# MCU.net
KiCad netlist of a schematic drawn in Altium Designer
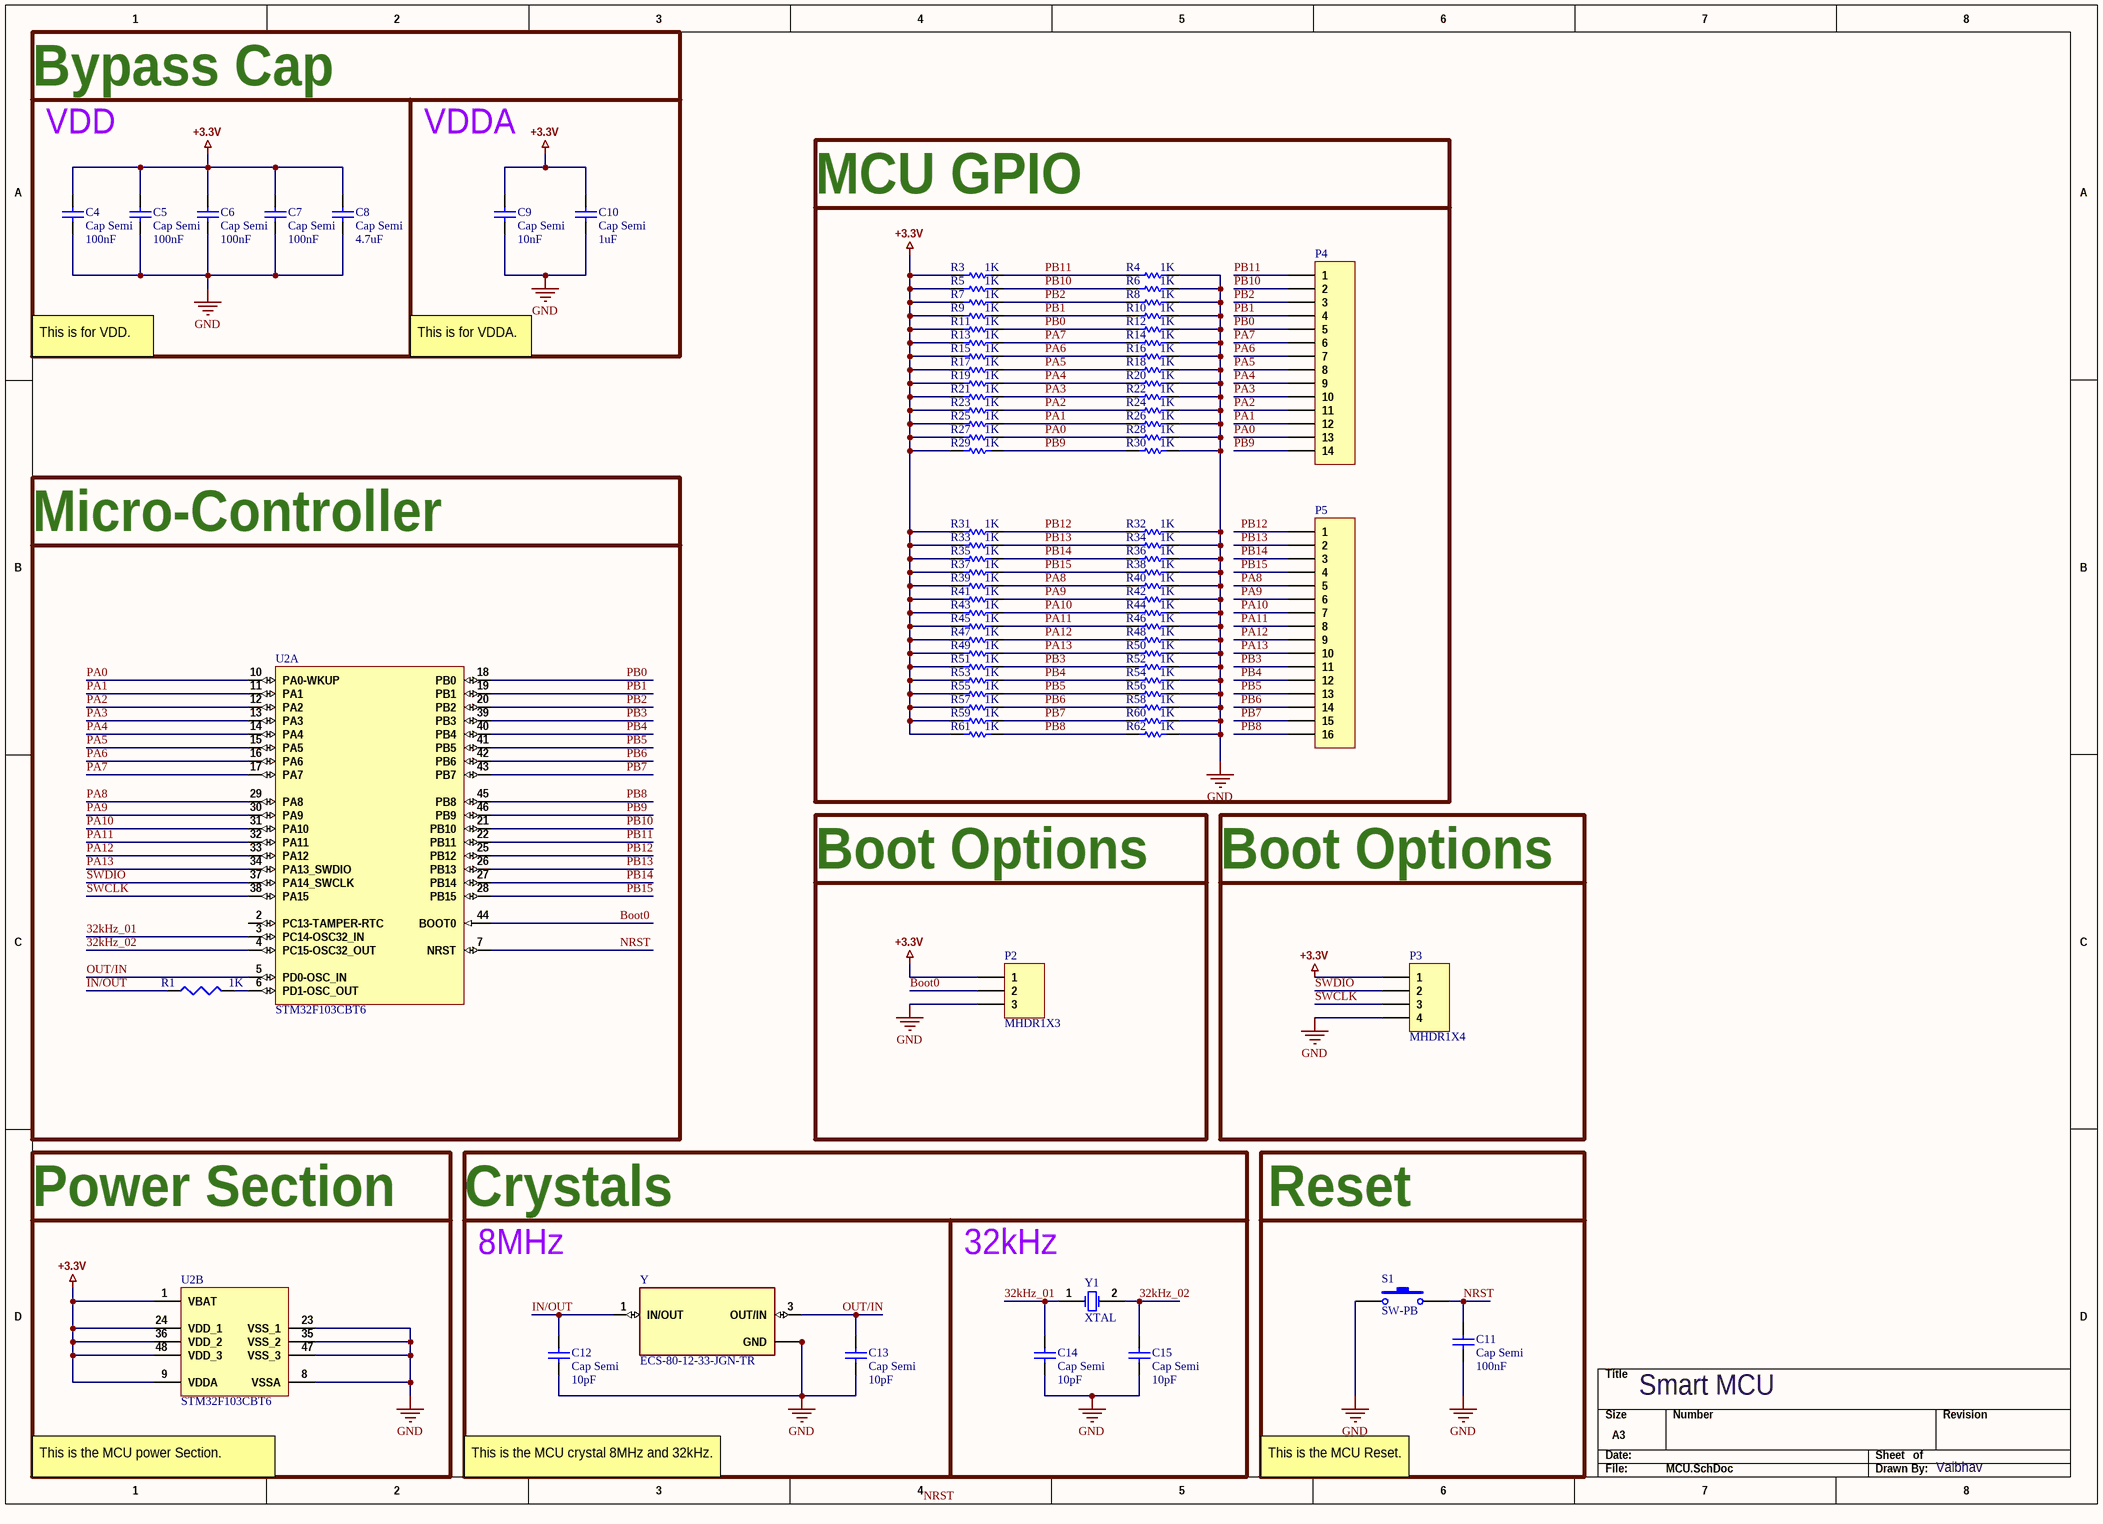
[diagram p0: MCU.SchDoc]

(export (version "E")
  (design (tool "Eeschema 10.0.6"))
  (components
    (comp (ref "C4")
      (value "Cap Semi")
      (footprint "1608[0603]")
      (description "Capacitor (Semiconductor SIM Model)")
      (fields (field (name "ALTIUM_VALUE") "100nF") (field (name "PUBLISHER") "Altium Limited"))
      (libsource (lib "Miscellaneous Devices") (part "Cap Semi"))
    )
    (comp (ref "C5")
      (value "Cap Semi")
      (footprint "1608[0603]")
      (description "Capacitor (Semiconductor SIM Model)")
      (fields (field (name "ALTIUM_VALUE") "100nF") (field (name "PUBLISHER") "Altium Limited"))
      (libsource (lib "Miscellaneous Devices") (part "Cap Semi"))
    )
    (comp (ref "C6")
      (value "Cap Semi")
      (footprint "1608[0603]")
      (description "Capacitor (Semiconductor SIM Model)")
      (fields (field (name "ALTIUM_VALUE") "100nF") (field (name "PUBLISHER") "Altium Limited"))
      (libsource (lib "Miscellaneous Devices") (part "Cap Semi"))
    )
    (comp (ref "C7")
      (value "Cap Semi")
      (footprint "1608[0603]")
      (description "Capacitor (Semiconductor SIM Model)")
      (fields (field (name "ALTIUM_VALUE") "100nF") (field (name "PUBLISHER") "Altium Limited"))
      (libsource (lib "Miscellaneous Devices") (part "Cap Semi"))
    )
    (comp (ref "C8")
      (value "Cap Semi")
      (footprint "1608[0603]")
      (description "Capacitor (Semiconductor SIM Model)")
      (fields (field (name "ALTIUM_VALUE") "4.7uF") (field (name "PUBLISHER") "Altium Limited"))
      (libsource (lib "Miscellaneous Devices") (part "Cap Semi"))
    )
    (comp (ref "C9")
      (value "Cap Semi")
      (footprint "1608[0603]")
      (description "Capacitor (Semiconductor SIM Model)")
      (fields (field (name "ALTIUM_VALUE") "10nF") (field (name "PUBLISHER") "Altium Limited"))
      (libsource (lib "Miscellaneous Devices") (part "Cap Semi"))
    )
    (comp (ref "C10")
      (value "Cap Semi")
      (footprint "1608[0603]")
      (description "Capacitor (Semiconductor SIM Model)")
      (fields (field (name "ALTIUM_VALUE") "1uF") (field (name "PUBLISHER") "Altium Limited"))
      (libsource (lib "Miscellaneous Devices") (part "Cap Semi"))
    )
    (comp (ref "C11")
      (value "Cap Semi")
      (footprint "1608[0603]")
      (description "Capacitor (Semiconductor SIM Model)")
      (fields (field (name "ALTIUM_VALUE") "100nF") (field (name "PUBLISHER") "Altium Limited"))
      (libsource (lib "Miscellaneous Devices") (part "Cap Semi"))
    )
    (comp (ref "C12")
      (value "Cap Semi")
      (footprint "0402")
      (description "Capacitor (Semiconductor SIM Model)")
      (fields (field (name "ALTIUM_VALUE") "10pF") (field (name "PUBLISHER") "Altium Limited"))
      (libsource (lib "Miscellaneous Devices") (part "Cap Semi"))
    )
    (comp (ref "C13")
      (value "Cap Semi")
      (footprint "0402")
      (description "Capacitor (Semiconductor SIM Model)")
      (fields (field (name "ALTIUM_VALUE") "10pF") (field (name "PUBLISHER") "Altium Limited"))
      (libsource (lib "Miscellaneous Devices") (part "Cap Semi"))
    )
    (comp (ref "C14")
      (value "Cap Semi")
      (footprint "0402")
      (description "Capacitor (Semiconductor SIM Model)")
      (fields (field (name "ALTIUM_VALUE") "10pF") (field (name "PUBLISHER") "Altium Limited"))
      (libsource (lib "Miscellaneous Devices") (part "Cap Semi"))
    )
    (comp (ref "C15")
      (value "Cap Semi")
      (footprint "0402")
      (description "Capacitor (Semiconductor SIM Model)")
      (fields (field (name "ALTIUM_VALUE") "10pF") (field (name "PUBLISHER") "Altium Limited"))
      (libsource (lib "Miscellaneous Devices") (part "Cap Semi"))
    )
    (comp (ref "P2")
      (value "MHDR1X3")
      (footprint "MHDR1X3")
      (description "Header, 3-Pin")
      (fields (field (name "PUBLISHER") "Altium Limited"))
      (libsource (lib "Miscellaneous Connectors") (part "MHDR1X3"))
    )
    (comp (ref "P3")
      (value "MHDR1X4")
      (footprint "MHDR1X4")
      (description "Header, 4-Pin")
      (fields (field (name "PUBLISHER") "Altium Limited"))
      (libsource (lib "Miscellaneous Connectors") (part "MHDR1X4"))
    )
    (comp (ref "P4")
      (value "Header 14")
      (footprint "MY_FE14")
      (description "Header, 14-Pin")
      (fields (field (name "ASID PART NUMBER") "Header 14-AS"))
      (libsource (lib "Mylib+Rev+4") (part "Header 14"))
    )
    (comp (ref "P5")
      (value "Header 16")
      (footprint "MY_FE16")
      (description "Header, 16-Pin")
      (fields (field (name "ASID PART NUMBER") "Header 16-AS"))
      (libsource (lib "Mylib+Rev+4") (part "Header 16"))
    )
    (comp (ref "R1")
      (value "1K")
      (footprint "J1-0603")
      (description "Resistor")
      (fields (field (name "Comment") "Res3") (field (name "PUBLISHER") "Altium Limited"))
      (libsource (lib "Miscellaneous Devices") (part "Res3"))
    )
    (comp (ref "R3")
      (value "1K")
      (footprint "MY_0603")
      (description "Standard resistor")
      (fields (field (name "ASID PART NUMBER") "Res-AS"))
      (libsource (lib "Mylib+Rev+4") (part "Res"))
    )
    (comp (ref "R4")
      (value "1K")
      (footprint "MY_0603")
      (description "Standard resistor")
      (fields (field (name "ASID PART NUMBER") "Res-AS"))
      (libsource (lib "Mylib+Rev+4") (part "Res"))
    )
    (comp (ref "R5")
      (value "1K")
      (footprint "MY_0603")
      (description "Standard resistor")
      (fields (field (name "ASID PART NUMBER") "Res-AS"))
      (libsource (lib "Mylib+Rev+4") (part "Res"))
    )
    (comp (ref "R6")
      (value "1K")
      (footprint "MY_0603")
      (description "Standard resistor")
      (fields (field (name "ASID PART NUMBER") "Res-AS"))
      (libsource (lib "Mylib+Rev+4") (part "Res"))
    )
    (comp (ref "R7")
      (value "1K")
      (footprint "MY_0603")
      (description "Standard resistor")
      (fields (field (name "ASID PART NUMBER") "Res-AS"))
      (libsource (lib "Mylib+Rev+4") (part "Res"))
    )
    (comp (ref "R8")
      (value "1K")
      (footprint "MY_0603")
      (description "Standard resistor")
      (fields (field (name "ASID PART NUMBER") "Res-AS"))
      (libsource (lib "Mylib+Rev+4") (part "Res"))
    )
    (comp (ref "R9")
      (value "1K")
      (footprint "MY_0603")
      (description "Standard resistor")
      (fields (field (name "ASID PART NUMBER") "Res-AS"))
      (libsource (lib "Mylib+Rev+4") (part "Res"))
    )
    (comp (ref "R10")
      (value "1K")
      (footprint "MY_0603")
      (description "Standard resistor")
      (fields (field (name "ASID PART NUMBER") "Res-AS"))
      (libsource (lib "Mylib+Rev+4") (part "Res"))
    )
    (comp (ref "R11")
      (value "1K")
      (footprint "MY_0603")
      (description "Standard resistor")
      (fields (field (name "ASID PART NUMBER") "Res-AS"))
      (libsource (lib "Mylib+Rev+4") (part "Res"))
    )
    (comp (ref "R12")
      (value "1K")
      (footprint "MY_0603")
      (description "Standard resistor")
      (fields (field (name "ASID PART NUMBER") "Res-AS"))
      (libsource (lib "Mylib+Rev+4") (part "Res"))
    )
    (comp (ref "R13")
      (value "1K")
      (footprint "MY_0603")
      (description "Standard resistor")
      (fields (field (name "ASID PART NUMBER") "Res-AS"))
      (libsource (lib "Mylib+Rev+4") (part "Res"))
    )
    (comp (ref "R14")
      (value "1K")
      (footprint "MY_0603")
      (description "Standard resistor")
      (fields (field (name "ASID PART NUMBER") "Res-AS"))
      (libsource (lib "Mylib+Rev+4") (part "Res"))
    )
    (comp (ref "R15")
      (value "1K")
      (footprint "MY_0603")
      (description "Standard resistor")
      (fields (field (name "ASID PART NUMBER") "Res-AS"))
      (libsource (lib "Mylib+Rev+4") (part "Res"))
    )
    (comp (ref "R16")
      (value "1K")
      (footprint "MY_0603")
      (description "Standard resistor")
      (fields (field (name "ASID PART NUMBER") "Res-AS"))
      (libsource (lib "Mylib+Rev+4") (part "Res"))
    )
    (comp (ref "R17")
      (value "1K")
      (footprint "MY_0603")
      (description "Standard resistor")
      (fields (field (name "ASID PART NUMBER") "Res-AS"))
      (libsource (lib "Mylib+Rev+4") (part "Res"))
    )
    (comp (ref "R18")
      (value "1K")
      (footprint "MY_0603")
      (description "Standard resistor")
      (fields (field (name "ASID PART NUMBER") "Res-AS"))
      (libsource (lib "Mylib+Rev+4") (part "Res"))
    )
    (comp (ref "R19")
      (value "1K")
      (footprint "MY_0603")
      (description "Standard resistor")
      (fields (field (name "ASID PART NUMBER") "Res-AS"))
      (libsource (lib "Mylib+Rev+4") (part "Res"))
    )
    (comp (ref "R20")
      (value "1K")
      (footprint "MY_0603")
      (description "Standard resistor")
      (fields (field (name "ASID PART NUMBER") "Res-AS"))
      (libsource (lib "Mylib+Rev+4") (part "Res"))
    )
    (comp (ref "R21")
      (value "1K")
      (footprint "MY_0603")
      (description "Standard resistor")
      (fields (field (name "ASID PART NUMBER") "Res-AS"))
      (libsource (lib "Mylib+Rev+4") (part "Res"))
    )
    (comp (ref "R22")
      (value "1K")
      (footprint "MY_0603")
      (description "Standard resistor")
      (fields (field (name "ASID PART NUMBER") "Res-AS"))
      (libsource (lib "Mylib+Rev+4") (part "Res"))
    )
    (comp (ref "R23")
      (value "1K")
      (footprint "MY_0603")
      (description "Standard resistor")
      (fields (field (name "ASID PART NUMBER") "Res-AS"))
      (libsource (lib "Mylib+Rev+4") (part "Res"))
    )
    (comp (ref "R24")
      (value "1K")
      (footprint "MY_0603")
      (description "Standard resistor")
      (fields (field (name "ASID PART NUMBER") "Res-AS"))
      (libsource (lib "Mylib+Rev+4") (part "Res"))
    )
    (comp (ref "R25")
      (value "1K")
      (footprint "MY_0603")
      (description "Standard resistor")
      (fields (field (name "ASID PART NUMBER") "Res-AS"))
      (libsource (lib "Mylib+Rev+4") (part "Res"))
    )
    (comp (ref "R26")
      (value "1K")
      (footprint "MY_0603")
      (description "Standard resistor")
      (fields (field (name "ASID PART NUMBER") "Res-AS"))
      (libsource (lib "Mylib+Rev+4") (part "Res"))
    )
    (comp (ref "R27")
      (value "1K")
      (footprint "MY_0603")
      (description "Standard resistor")
      (fields (field (name "ASID PART NUMBER") "Res-AS"))
      (libsource (lib "Mylib+Rev+4") (part "Res"))
    )
    (comp (ref "R28")
      (value "1K")
      (footprint "MY_0603")
      (description "Standard resistor")
      (fields (field (name "ASID PART NUMBER") "Res-AS"))
      (libsource (lib "Mylib+Rev+4") (part "Res"))
    )
    (comp (ref "R29")
      (value "1K")
      (footprint "MY_0603")
      (description "Standard resistor")
      (fields (field (name "ASID PART NUMBER") "Res-AS"))
      (libsource (lib "Mylib+Rev+4") (part "Res"))
    )
    (comp (ref "R30")
      (value "1K")
      (footprint "MY_0603")
      (description "Standard resistor")
      (fields (field (name "ASID PART NUMBER") "Res-AS"))
      (libsource (lib "Mylib+Rev+4") (part "Res"))
    )
    (comp (ref "R31")
      (value "1K")
      (footprint "MY_0603")
      (description "Standard resistor")
      (fields (field (name "ASID PART NUMBER") "Res-AS"))
      (libsource (lib "Mylib+Rev+4") (part "Res"))
    )
    (comp (ref "R32")
      (value "1K")
      (footprint "MY_0603")
      (description "Standard resistor")
      (fields (field (name "ASID PART NUMBER") "Res-AS"))
      (libsource (lib "Mylib+Rev+4") (part "Res"))
    )
    (comp (ref "R33")
      (value "1K")
      (footprint "MY_0603")
      (description "Standard resistor")
      (fields (field (name "ASID PART NUMBER") "Res-AS"))
      (libsource (lib "Mylib+Rev+4") (part "Res"))
    )
    (comp (ref "R34")
      (value "1K")
      (footprint "MY_0603")
      (description "Standard resistor")
      (fields (field (name "ASID PART NUMBER") "Res-AS"))
      (libsource (lib "Mylib+Rev+4") (part "Res"))
    )
    (comp (ref "R35")
      (value "1K")
      (footprint "MY_0603")
      (description "Standard resistor")
      (fields (field (name "ASID PART NUMBER") "Res-AS"))
      (libsource (lib "Mylib+Rev+4") (part "Res"))
    )
    (comp (ref "R36")
      (value "1K")
      (footprint "MY_0603")
      (description "Standard resistor")
      (fields (field (name "ASID PART NUMBER") "Res-AS"))
      (libsource (lib "Mylib+Rev+4") (part "Res"))
    )
    (comp (ref "R37")
      (value "1K")
      (footprint "MY_0603")
      (description "Standard resistor")
      (fields (field (name "ASID PART NUMBER") "Res-AS"))
      (libsource (lib "Mylib+Rev+4") (part "Res"))
    )
    (comp (ref "R38")
      (value "1K")
      (footprint "MY_0603")
      (description "Standard resistor")
      (fields (field (name "ASID PART NUMBER") "Res-AS"))
      (libsource (lib "Mylib+Rev+4") (part "Res"))
    )
    (comp (ref "R39")
      (value "1K")
      (footprint "MY_0603")
      (description "Standard resistor")
      (fields (field (name "ASID PART NUMBER") "Res-AS"))
      (libsource (lib "Mylib+Rev+4") (part "Res"))
    )
    (comp (ref "R40")
      (value "1K")
      (footprint "MY_0603")
      (description "Standard resistor")
      (fields (field (name "ASID PART NUMBER") "Res-AS"))
      (libsource (lib "Mylib+Rev+4") (part "Res"))
    )
    (comp (ref "R41")
      (value "1K")
      (footprint "MY_0603")
      (description "Standard resistor")
      (fields (field (name "ASID PART NUMBER") "Res-AS"))
      (libsource (lib "Mylib+Rev+4") (part "Res"))
    )
    (comp (ref "R42")
      (value "1K")
      (footprint "MY_0603")
      (description "Standard resistor")
      (fields (field (name "ASID PART NUMBER") "Res-AS"))
      (libsource (lib "Mylib+Rev+4") (part "Res"))
    )
    (comp (ref "R43")
      (value "1K")
      (footprint "MY_0603")
      (description "Standard resistor")
      (fields (field (name "ASID PART NUMBER") "Res-AS"))
      (libsource (lib "Mylib+Rev+4") (part "Res"))
    )
    (comp (ref "R44")
      (value "1K")
      (footprint "MY_0603")
      (description "Standard resistor")
      (fields (field (name "ASID PART NUMBER") "Res-AS"))
      (libsource (lib "Mylib+Rev+4") (part "Res"))
    )
    (comp (ref "R45")
      (value "1K")
      (footprint "MY_0603")
      (description "Standard resistor")
      (fields (field (name "ASID PART NUMBER") "Res-AS"))
      (libsource (lib "Mylib+Rev+4") (part "Res"))
    )
    (comp (ref "R46")
      (value "1K")
      (footprint "MY_0603")
      (description "Standard resistor")
      (fields (field (name "ASID PART NUMBER") "Res-AS"))
      (libsource (lib "Mylib+Rev+4") (part "Res"))
    )
    (comp (ref "R47")
      (value "1K")
      (footprint "MY_0603")
      (description "Standard resistor")
      (fields (field (name "ASID PART NUMBER") "Res-AS"))
      (libsource (lib "Mylib+Rev+4") (part "Res"))
    )
    (comp (ref "R48")
      (value "1K")
      (footprint "MY_0603")
      (description "Standard resistor")
      (fields (field (name "ASID PART NUMBER") "Res-AS"))
      (libsource (lib "Mylib+Rev+4") (part "Res"))
    )
    (comp (ref "R49")
      (value "1K")
      (footprint "MY_0603")
      (description "Standard resistor")
      (fields (field (name "ASID PART NUMBER") "Res-AS"))
      (libsource (lib "Mylib+Rev+4") (part "Res"))
    )
    (comp (ref "R50")
      (value "1K")
      (footprint "MY_0603")
      (description "Standard resistor")
      (fields (field (name "ASID PART NUMBER") "Res-AS"))
      (libsource (lib "Mylib+Rev+4") (part "Res"))
    )
    (comp (ref "R51")
      (value "1K")
      (footprint "MY_0603")
      (description "Standard resistor")
      (fields (field (name "ASID PART NUMBER") "Res-AS"))
      (libsource (lib "Mylib+Rev+4") (part "Res"))
    )
    (comp (ref "R52")
      (value "1K")
      (footprint "MY_0603")
      (description "Standard resistor")
      (fields (field (name "ASID PART NUMBER") "Res-AS"))
      (libsource (lib "Mylib+Rev+4") (part "Res"))
    )
    (comp (ref "R53")
      (value "1K")
      (footprint "MY_0603")
      (description "Standard resistor")
      (fields (field (name "ASID PART NUMBER") "Res-AS"))
      (libsource (lib "Mylib+Rev+4") (part "Res"))
    )
    (comp (ref "R54")
      (value "1K")
      (footprint "MY_0603")
      (description "Standard resistor")
      (fields (field (name "ASID PART NUMBER") "Res-AS"))
      (libsource (lib "Mylib+Rev+4") (part "Res"))
    )
    (comp (ref "R55")
      (value "1K")
      (footprint "MY_0603")
      (description "Standard resistor")
      (fields (field (name "ASID PART NUMBER") "Res-AS"))
      (libsource (lib "Mylib+Rev+4") (part "Res"))
    )
    (comp (ref "R56")
      (value "1K")
      (footprint "MY_0603")
      (description "Standard resistor")
      (fields (field (name "ASID PART NUMBER") "Res-AS"))
      (libsource (lib "Mylib+Rev+4") (part "Res"))
    )
    (comp (ref "R57")
      (value "1K")
      (footprint "MY_0603")
      (description "Standard resistor")
      (fields (field (name "ASID PART NUMBER") "Res-AS"))
      (libsource (lib "Mylib+Rev+4") (part "Res"))
    )
    (comp (ref "R58")
      (value "1K")
      (footprint "MY_0603")
      (description "Standard resistor")
      (fields (field (name "ASID PART NUMBER") "Res-AS"))
      (libsource (lib "Mylib+Rev+4") (part "Res"))
    )
    (comp (ref "R59")
      (value "1K")
      (footprint "MY_0603")
      (description "Standard resistor")
      (fields (field (name "ASID PART NUMBER") "Res-AS"))
      (libsource (lib "Mylib+Rev+4") (part "Res"))
    )
    (comp (ref "R60")
      (value "1K")
      (footprint "MY_0603")
      (description "Standard resistor")
      (fields (field (name "ASID PART NUMBER") "Res-AS"))
      (libsource (lib "Mylib+Rev+4") (part "Res"))
    )
    (comp (ref "R61")
      (value "1K")
      (footprint "MY_0603")
      (description "Standard resistor")
      (fields (field (name "ASID PART NUMBER") "Res-AS"))
      (libsource (lib "Mylib+Rev+4") (part "Res"))
    )
    (comp (ref "R62")
      (value "1K")
      (footprint "MY_0603")
      (description "Standard resistor")
      (fields (field (name "ASID PART NUMBER") "Res-AS"))
      (libsource (lib "Mylib+Rev+4") (part "Res"))
    )
    (comp (ref "S1")
      (value "SW-PB")
      (footprint "SPST-2")
      (description "Switch")
      (fields (field (name "PUBLISHER") "Altium Limited"))
      (libsource (lib "Miscellaneous Devices") (part "SW-PB"))
    )
    (comp (ref "U2")
      (value "STM32F103CBT6")
      (footprint "STM-LQFP48_N")
      (libsource (lib "STMicroelectronics STM32 F1") (part "STM32F103CBT6"))
    )
    (comp (ref "Y")
      (value "ECS-80-12-33-JGN-TR")
      (footprint "XTAL_ECS-240-8-33-AGN-TR")
      (description "8MHz Â±20ppm Crystal 12pF 400 Ohms 4-SMD, No Lead")
      (fields
        (field (name "MF") "ECS Inc.")
        (field (name "BUYPART") "https://www.snapeda.com/parts/ECS-80-12-33-JGN-TR/ECS%20Inc./view-part/4477300/?ref=eda")
      )
      (libsource (lib "ECS-80-12-33-JGN-TR") (part "ECS-80-12-33-JGN-TR"))
    )
    (comp (ref "Y1")
      (value "XTAL")
      (footprint "R38")
      (description "Crystal Oscillator")
      (fields (field (name "PUBLISHER") "Altium Limited"))
      (libsource (lib "Miscellaneous Devices") (part "XTAL"))
    )
  )
  (nets
    (net (code "1") (name "+3.3V") (class "Default")
      (node (ref "C10") (pin "2") (pinfunction "2_2") (pintype "passive"))
      (node (ref "C4") (pin "2") (pinfunction "2_2") (pintype "passive"))
      (node (ref "C5") (pin "2") (pinfunction "2_2") (pintype "passive"))
      (node (ref "C6") (pin "2") (pinfunction "2_2") (pintype "passive"))
      (node (ref "C7") (pin "2") (pinfunction "2_2") (pintype "passive"))
      (node (ref "C8") (pin "2") (pinfunction "2_2") (pintype "passive"))
      (node (ref "C9") (pin "2") (pinfunction "2_2") (pintype "passive"))
      (node (ref "P2") (pin "1") (pinfunction "1_1") (pintype "passive"))
      (node (ref "P3") (pin "1") (pinfunction "1_1") (pintype "passive"))
      (node (ref "R11") (pin "1") (pinfunction "1_1") (pintype "passive"))
      (node (ref "R13") (pin "1") (pinfunction "1_1") (pintype "passive"))
      (node (ref "R15") (pin "1") (pinfunction "1_1") (pintype "passive"))
      (node (ref "R17") (pin "1") (pinfunction "1_1") (pintype "passive"))
      (node (ref "R19") (pin "1") (pinfunction "1_1") (pintype "passive"))
      (node (ref "R21") (pin "1") (pinfunction "1_1") (pintype "passive"))
      (node (ref "R23") (pin "1") (pinfunction "1_1") (pintype "passive"))
      (node (ref "R25") (pin "1") (pinfunction "1_1") (pintype "passive"))
      (node (ref "R27") (pin "1") (pinfunction "1_1") (pintype "passive"))
      (node (ref "R29") (pin "1") (pinfunction "1_1") (pintype "passive"))
      (node (ref "R3") (pin "1") (pinfunction "1_1") (pintype "passive"))
      (node (ref "R31") (pin "1") (pinfunction "1_1") (pintype "passive"))
      (node (ref "R33") (pin "1") (pinfunction "1_1") (pintype "passive"))
      (node (ref "R35") (pin "1") (pinfunction "1_1") (pintype "passive"))
      (node (ref "R37") (pin "1") (pinfunction "1_1") (pintype "passive"))
      (node (ref "R39") (pin "1") (pinfunction "1_1") (pintype "passive"))
      (node (ref "R41") (pin "1") (pinfunction "1_1") (pintype "passive"))
      (node (ref "R43") (pin "1") (pinfunction "1_1") (pintype "passive"))
      (node (ref "R45") (pin "1") (pinfunction "1_1") (pintype "passive"))
      (node (ref "R47") (pin "1") (pinfunction "1_1") (pintype "passive"))
      (node (ref "R49") (pin "1") (pinfunction "1_1") (pintype "passive"))
      (node (ref "R5") (pin "1") (pinfunction "1_1") (pintype "passive"))
      (node (ref "R51") (pin "1") (pinfunction "1_1") (pintype "passive"))
      (node (ref "R53") (pin "1") (pinfunction "1_1") (pintype "passive"))
      (node (ref "R55") (pin "1") (pinfunction "1_1") (pintype "passive"))
      (node (ref "R57") (pin "1") (pinfunction "1_1") (pintype "passive"))
      (node (ref "R59") (pin "1") (pinfunction "1_1") (pintype "passive"))
      (node (ref "R61") (pin "1") (pinfunction "1_1") (pintype "passive"))
      (node (ref "R7") (pin "1") (pinfunction "1_1") (pintype "passive"))
      (node (ref "R9") (pin "1") (pinfunction "1_1") (pintype "passive"))
      (node (ref "U2") (pin "1") (pinfunction "VBAT_1") (pintype "power_in"))
      (node (ref "U2") (pin "24") (pinfunction "VDD_1_24") (pintype "power_in"))
      (node (ref "U2") (pin "36") (pinfunction "VDD_2_36") (pintype "power_in"))
      (node (ref "U2") (pin "48") (pinfunction "VDD_3_48") (pintype "power_in"))
      (node (ref "U2") (pin "9") (pinfunction "VDDA_9") (pintype "power_in"))
    )
    (net (code "2") (name "/32kHz_01") (class "Default")
      (node (ref "C14") (pin "2") (pinfunction "2_2") (pintype "passive"))
      (node (ref "U2") (pin "3") (pinfunction "PC14-OSC32_IN_3") (pintype "bidirectional"))
      (node (ref "Y1") (pin "1") (pinfunction "OSC1_1") (pintype "passive"))
    )
    (net (code "3") (name "/32kHz_02") (class "Default")
      (node (ref "C15") (pin "2") (pinfunction "2_2") (pintype "passive"))
      (node (ref "U2") (pin "4") (pinfunction "PC15-OSC32_OUT_4") (pintype "bidirectional"))
      (node (ref "Y1") (pin "2") (pinfunction "OSC2_2") (pintype "passive"))
    )
    (net (code "4") (name "/Boot0") (class "Default")
      (node (ref "P2") (pin "2") (pinfunction "2_2") (pintype "passive"))
      (node (ref "U2") (pin "44") (pinfunction "BOOT0_44") (pintype "input"))
    )
    (net (code "5") (name "/IN{slash}OUT") (class "Default")
      (node (ref "C12") (pin "2") (pinfunction "2_2") (pintype "passive"))
      (node (ref "R1") (pin "1") (pinfunction "1_1") (pintype "passive"))
      (node (ref "Y") (pin "1") (pinfunction "IN/OUT_1") (pintype "bidirectional"))
    )
    (net (code "6") (name "/NRST") (class "Default")
      (node (ref "C11") (pin "2") (pinfunction "2_2") (pintype "passive"))
      (node (ref "S1") (pin "2") (pinfunction "2_2") (pintype "passive"))
      (node (ref "U2") (pin "7") (pinfunction "NRST_7") (pintype "bidirectional"))
    )
    (net (code "7") (name "/OUT{slash}IN") (class "Default")
      (node (ref "C13") (pin "2") (pinfunction "2_2") (pintype "passive"))
      (node (ref "U2") (pin "5") (pinfunction "PD0-OSC_IN_5") (pintype "bidirectional"))
      (node (ref "Y") (pin "3") (pinfunction "OUT/IN_3") (pintype "bidirectional"))
    )
    (net (code "8") (name "/PA0") (class "Default")
      (node (ref "P4") (pin "13") (pinfunction "13_13") (pintype "passive"))
      (node (ref "R27") (pin "2") (pinfunction "2_2") (pintype "passive"))
      (node (ref "R28") (pin "1") (pinfunction "1_1") (pintype "passive"))
      (node (ref "U2") (pin "10") (pinfunction "PA0-WKUP_10") (pintype "bidirectional"))
    )
    (net (code "9") (name "/PA1") (class "Default")
      (node (ref "P4") (pin "12") (pinfunction "12_12") (pintype "passive"))
      (node (ref "R25") (pin "2") (pinfunction "2_2") (pintype "passive"))
      (node (ref "R26") (pin "1") (pinfunction "1_1") (pintype "passive"))
      (node (ref "U2") (pin "11") (pinfunction "PA1_11") (pintype "bidirectional"))
    )
    (net (code "10") (name "/PA2") (class "Default")
      (node (ref "P4") (pin "11") (pinfunction "11_11") (pintype "passive"))
      (node (ref "R23") (pin "2") (pinfunction "2_2") (pintype "passive"))
      (node (ref "R24") (pin "1") (pinfunction "1_1") (pintype "passive"))
      (node (ref "U2") (pin "12") (pinfunction "PA2_12") (pintype "bidirectional"))
    )
    (net (code "11") (name "/PA3") (class "Default")
      (node (ref "P4") (pin "10") (pinfunction "10_10") (pintype "passive"))
      (node (ref "R21") (pin "2") (pinfunction "2_2") (pintype "passive"))
      (node (ref "R22") (pin "1") (pinfunction "1_1") (pintype "passive"))
      (node (ref "U2") (pin "13") (pinfunction "PA3_13") (pintype "bidirectional"))
    )
    (net (code "12") (name "/PA4") (class "Default")
      (node (ref "P4") (pin "9") (pinfunction "9_9") (pintype "passive"))
      (node (ref "R19") (pin "2") (pinfunction "2_2") (pintype "passive"))
      (node (ref "R20") (pin "1") (pinfunction "1_1") (pintype "passive"))
      (node (ref "U2") (pin "14") (pinfunction "PA4_14") (pintype "bidirectional"))
    )
    (net (code "13") (name "/PA5") (class "Default")
      (node (ref "P4") (pin "8") (pinfunction "8_8") (pintype "passive"))
      (node (ref "R17") (pin "2") (pinfunction "2_2") (pintype "passive"))
      (node (ref "R18") (pin "1") (pinfunction "1_1") (pintype "passive"))
      (node (ref "U2") (pin "15") (pinfunction "PA5_15") (pintype "bidirectional"))
    )
    (net (code "14") (name "/PA6") (class "Default")
      (node (ref "P4") (pin "7") (pinfunction "7_7") (pintype "passive"))
      (node (ref "R15") (pin "2") (pinfunction "2_2") (pintype "passive"))
      (node (ref "R16") (pin "1") (pinfunction "1_1") (pintype "passive"))
      (node (ref "U2") (pin "16") (pinfunction "PA6_16") (pintype "bidirectional"))
    )
    (net (code "15") (name "/PA7") (class "Default")
      (node (ref "P4") (pin "6") (pinfunction "6_6") (pintype "passive"))
      (node (ref "R13") (pin "2") (pinfunction "2_2") (pintype "passive"))
      (node (ref "R14") (pin "1") (pinfunction "1_1") (pintype "passive"))
      (node (ref "U2") (pin "17") (pinfunction "PA7_17") (pintype "bidirectional"))
    )
    (net (code "16") (name "/PA8") (class "Default")
      (node (ref "P5") (pin "5") (pinfunction "5_5") (pintype "passive"))
      (node (ref "R39") (pin "2") (pinfunction "2_2") (pintype "passive"))
      (node (ref "R40") (pin "1") (pinfunction "1_1") (pintype "passive"))
      (node (ref "U2") (pin "29") (pinfunction "PA8_29") (pintype "bidirectional"))
    )
    (net (code "17") (name "/PA9") (class "Default")
      (node (ref "P5") (pin "6") (pinfunction "6_6") (pintype "passive"))
      (node (ref "R41") (pin "2") (pinfunction "2_2") (pintype "passive"))
      (node (ref "R42") (pin "1") (pinfunction "1_1") (pintype "passive"))
      (node (ref "U2") (pin "30") (pinfunction "PA9_30") (pintype "bidirectional"))
    )
    (net (code "18") (name "/PA10") (class "Default")
      (node (ref "P5") (pin "7") (pinfunction "7_7") (pintype "passive"))
      (node (ref "R43") (pin "2") (pinfunction "2_2") (pintype "passive"))
      (node (ref "R44") (pin "1") (pinfunction "1_1") (pintype "passive"))
      (node (ref "U2") (pin "31") (pinfunction "PA10_31") (pintype "bidirectional"))
    )
    (net (code "19") (name "/PA11") (class "Default")
      (node (ref "P5") (pin "8") (pinfunction "8_8") (pintype "passive"))
      (node (ref "R45") (pin "2") (pinfunction "2_2") (pintype "passive"))
      (node (ref "R46") (pin "1") (pinfunction "1_1") (pintype "passive"))
      (node (ref "U2") (pin "32") (pinfunction "PA11_32") (pintype "bidirectional"))
    )
    (net (code "20") (name "/PA12") (class "Default")
      (node (ref "P5") (pin "9") (pinfunction "9_9") (pintype "passive"))
      (node (ref "R47") (pin "2") (pinfunction "2_2") (pintype "passive"))
      (node (ref "R48") (pin "1") (pinfunction "1_1") (pintype "passive"))
      (node (ref "U2") (pin "33") (pinfunction "PA12_33") (pintype "bidirectional"))
    )
    (net (code "21") (name "/PA13") (class "Default")
      (node (ref "P5") (pin "10") (pinfunction "10_10") (pintype "passive"))
      (node (ref "R49") (pin "2") (pinfunction "2_2") (pintype "passive"))
      (node (ref "R50") (pin "1") (pinfunction "1_1") (pintype "passive"))
      (node (ref "U2") (pin "34") (pinfunction "PA13_SWDIO_34") (pintype "bidirectional"))
    )
    (net (code "22") (name "/PB0") (class "Default")
      (node (ref "P4") (pin "5") (pinfunction "5_5") (pintype "passive"))
      (node (ref "R11") (pin "2") (pinfunction "2_2") (pintype "passive"))
      (node (ref "R12") (pin "1") (pinfunction "1_1") (pintype "passive"))
      (node (ref "U2") (pin "18") (pinfunction "PB0_18") (pintype "bidirectional"))
    )
    (net (code "23") (name "/PB1") (class "Default")
      (node (ref "P4") (pin "4") (pinfunction "4_4") (pintype "passive"))
      (node (ref "R10") (pin "1") (pinfunction "1_1") (pintype "passive"))
      (node (ref "R9") (pin "2") (pinfunction "2_2") (pintype "passive"))
      (node (ref "U2") (pin "19") (pinfunction "PB1_19") (pintype "bidirectional"))
    )
    (net (code "24") (name "/PB2") (class "Default")
      (node (ref "P4") (pin "3") (pinfunction "3_3") (pintype "passive"))
      (node (ref "R7") (pin "2") (pinfunction "2_2") (pintype "passive"))
      (node (ref "R8") (pin "1") (pinfunction "1_1") (pintype "passive"))
      (node (ref "U2") (pin "20") (pinfunction "PB2_20") (pintype "bidirectional"))
    )
    (net (code "25") (name "/PB3") (class "Default")
      (node (ref "P5") (pin "11") (pinfunction "11_11") (pintype "passive"))
      (node (ref "R51") (pin "2") (pinfunction "2_2") (pintype "passive"))
      (node (ref "R52") (pin "1") (pinfunction "1_1") (pintype "passive"))
      (node (ref "U2") (pin "39") (pinfunction "PB3_39") (pintype "bidirectional"))
    )
    (net (code "26") (name "/PB4") (class "Default")
      (node (ref "P5") (pin "12") (pinfunction "12_12") (pintype "passive"))
      (node (ref "R53") (pin "2") (pinfunction "2_2") (pintype "passive"))
      (node (ref "R54") (pin "1") (pinfunction "1_1") (pintype "passive"))
      (node (ref "U2") (pin "40") (pinfunction "PB4_40") (pintype "bidirectional"))
    )
    (net (code "27") (name "/PB5") (class "Default")
      (node (ref "P5") (pin "13") (pinfunction "13_13") (pintype "passive"))
      (node (ref "R55") (pin "2") (pinfunction "2_2") (pintype "passive"))
      (node (ref "R56") (pin "1") (pinfunction "1_1") (pintype "passive"))
      (node (ref "U2") (pin "41") (pinfunction "PB5_41") (pintype "bidirectional"))
    )
    (net (code "28") (name "/PB6") (class "Default")
      (node (ref "P5") (pin "14") (pinfunction "14_14") (pintype "passive"))
      (node (ref "R57") (pin "2") (pinfunction "2_2") (pintype "passive"))
      (node (ref "R58") (pin "1") (pinfunction "1_1") (pintype "passive"))
      (node (ref "U2") (pin "42") (pinfunction "PB6_42") (pintype "bidirectional"))
    )
    (net (code "29") (name "/PB7") (class "Default")
      (node (ref "P5") (pin "15") (pinfunction "15_15") (pintype "passive"))
      (node (ref "R59") (pin "2") (pinfunction "2_2") (pintype "passive"))
      (node (ref "R60") (pin "1") (pinfunction "1_1") (pintype "passive"))
      (node (ref "U2") (pin "43") (pinfunction "PB7_43") (pintype "bidirectional"))
    )
    (net (code "30") (name "/PB8") (class "Default")
      (node (ref "P5") (pin "16") (pinfunction "16_16") (pintype "passive"))
      (node (ref "R61") (pin "2") (pinfunction "2_2") (pintype "passive"))
      (node (ref "R62") (pin "1") (pinfunction "1_1") (pintype "passive"))
      (node (ref "U2") (pin "45") (pinfunction "PB8_45") (pintype "bidirectional"))
    )
    (net (code "31") (name "/PB9") (class "Default")
      (node (ref "P4") (pin "14") (pinfunction "14_14") (pintype "passive"))
      (node (ref "R29") (pin "2") (pinfunction "2_2") (pintype "passive"))
      (node (ref "R30") (pin "1") (pinfunction "1_1") (pintype "passive"))
      (node (ref "U2") (pin "46") (pinfunction "PB9_46") (pintype "bidirectional"))
    )
    (net (code "32") (name "/PB10") (class "Default")
      (node (ref "P4") (pin "2") (pinfunction "2_2") (pintype "passive"))
      (node (ref "R5") (pin "2") (pinfunction "2_2") (pintype "passive"))
      (node (ref "R6") (pin "1") (pinfunction "1_1") (pintype "passive"))
      (node (ref "U2") (pin "21") (pinfunction "PB10_21") (pintype "bidirectional"))
    )
    (net (code "33") (name "/PB11") (class "Default")
      (node (ref "P4") (pin "1") (pinfunction "1_1") (pintype "passive"))
      (node (ref "R3") (pin "2") (pinfunction "2_2") (pintype "passive"))
      (node (ref "R4") (pin "1") (pinfunction "1_1") (pintype "passive"))
      (node (ref "U2") (pin "22") (pinfunction "PB11_22") (pintype "bidirectional"))
    )
    (net (code "34") (name "/PB12") (class "Default")
      (node (ref "P5") (pin "1") (pinfunction "1_1") (pintype "passive"))
      (node (ref "R31") (pin "2") (pinfunction "2_2") (pintype "passive"))
      (node (ref "R32") (pin "1") (pinfunction "1_1") (pintype "passive"))
      (node (ref "U2") (pin "25") (pinfunction "PB12_25") (pintype "bidirectional"))
    )
    (net (code "35") (name "/PB13") (class "Default")
      (node (ref "P5") (pin "2") (pinfunction "2_2") (pintype "passive"))
      (node (ref "R33") (pin "2") (pinfunction "2_2") (pintype "passive"))
      (node (ref "R34") (pin "1") (pinfunction "1_1") (pintype "passive"))
      (node (ref "U2") (pin "26") (pinfunction "PB13_26") (pintype "bidirectional"))
    )
    (net (code "36") (name "/PB14") (class "Default")
      (node (ref "P5") (pin "3") (pinfunction "3_3") (pintype "passive"))
      (node (ref "R35") (pin "2") (pinfunction "2_2") (pintype "passive"))
      (node (ref "R36") (pin "1") (pinfunction "1_1") (pintype "passive"))
      (node (ref "U2") (pin "27") (pinfunction "PB14_27") (pintype "bidirectional"))
    )
    (net (code "37") (name "/PB15") (class "Default")
      (node (ref "P5") (pin "4") (pinfunction "4_4") (pintype "passive"))
      (node (ref "R37") (pin "2") (pinfunction "2_2") (pintype "passive"))
      (node (ref "R38") (pin "1") (pinfunction "1_1") (pintype "passive"))
      (node (ref "U2") (pin "28") (pinfunction "PB15_28") (pintype "bidirectional"))
    )
    (net (code "38") (name "/SWCLK") (class "Default")
      (node (ref "P3") (pin "3") (pinfunction "3_3") (pintype "passive"))
      (node (ref "U2") (pin "38") (pinfunction "PA15_38") (pintype "bidirectional"))
    )
    (net (code "39") (name "/SWDIO") (class "Default")
      (node (ref "P3") (pin "2") (pinfunction "2_2") (pintype "passive"))
      (node (ref "U2") (pin "37") (pinfunction "PA14_SWCLK_37") (pintype "bidirectional"))
    )
    (net (code "40") (name "GND") (class "Default")
      (node (ref "C10") (pin "1") (pinfunction "1_1") (pintype "passive"))
      (node (ref "C11") (pin "1") (pinfunction "1_1") (pintype "passive"))
      (node (ref "C12") (pin "1") (pinfunction "1_1") (pintype "passive"))
      (node (ref "C13") (pin "1") (pinfunction "1_1") (pintype "passive"))
      (node (ref "C14") (pin "1") (pinfunction "1_1") (pintype "passive"))
      (node (ref "C15") (pin "1") (pinfunction "1_1") (pintype "passive"))
      (node (ref "C4") (pin "1") (pinfunction "1_1") (pintype "passive"))
      (node (ref "C5") (pin "1") (pinfunction "1_1") (pintype "passive"))
      (node (ref "C6") (pin "1") (pinfunction "1_1") (pintype "passive"))
      (node (ref "C7") (pin "1") (pinfunction "1_1") (pintype "passive"))
      (node (ref "C8") (pin "1") (pinfunction "1_1") (pintype "passive"))
      (node (ref "C9") (pin "1") (pinfunction "1_1") (pintype "passive"))
      (node (ref "P2") (pin "3") (pinfunction "3_3") (pintype "passive"))
      (node (ref "P3") (pin "4") (pinfunction "4_4") (pintype "passive"))
      (node (ref "R10") (pin "2") (pinfunction "2_2") (pintype "passive"))
      (node (ref "R12") (pin "2") (pinfunction "2_2") (pintype "passive"))
      (node (ref "R14") (pin "2") (pinfunction "2_2") (pintype "passive"))
      (node (ref "R16") (pin "2") (pinfunction "2_2") (pintype "passive"))
      (node (ref "R18") (pin "2") (pinfunction "2_2") (pintype "passive"))
      (node (ref "R20") (pin "2") (pinfunction "2_2") (pintype "passive"))
      (node (ref "R22") (pin "2") (pinfunction "2_2") (pintype "passive"))
      (node (ref "R24") (pin "2") (pinfunction "2_2") (pintype "passive"))
      (node (ref "R26") (pin "2") (pinfunction "2_2") (pintype "passive"))
      (node (ref "R28") (pin "2") (pinfunction "2_2") (pintype "passive"))
      (node (ref "R30") (pin "2") (pinfunction "2_2") (pintype "passive"))
      (node (ref "R32") (pin "2") (pinfunction "2_2") (pintype "passive"))
      (node (ref "R34") (pin "2") (pinfunction "2_2") (pintype "passive"))
      (node (ref "R36") (pin "2") (pinfunction "2_2") (pintype "passive"))
      (node (ref "R38") (pin "2") (pinfunction "2_2") (pintype "passive"))
      (node (ref "R4") (pin "2") (pinfunction "2_2") (pintype "passive"))
      (node (ref "R40") (pin "2") (pinfunction "2_2") (pintype "passive"))
      (node (ref "R42") (pin "2") (pinfunction "2_2") (pintype "passive"))
      (node (ref "R44") (pin "2") (pinfunction "2_2") (pintype "passive"))
      (node (ref "R46") (pin "2") (pinfunction "2_2") (pintype "passive"))
      (node (ref "R48") (pin "2") (pinfunction "2_2") (pintype "passive"))
      (node (ref "R50") (pin "2") (pinfunction "2_2") (pintype "passive"))
      (node (ref "R52") (pin "2") (pinfunction "2_2") (pintype "passive"))
      (node (ref "R54") (pin "2") (pinfunction "2_2") (pintype "passive"))
      (node (ref "R56") (pin "2") (pinfunction "2_2") (pintype "passive"))
      (node (ref "R58") (pin "2") (pinfunction "2_2") (pintype "passive"))
      (node (ref "R6") (pin "2") (pinfunction "2_2") (pintype "passive"))
      (node (ref "R60") (pin "2") (pinfunction "2_2") (pintype "passive"))
      (node (ref "R62") (pin "2") (pinfunction "2_2") (pintype "passive"))
      (node (ref "R8") (pin "2") (pinfunction "2_2") (pintype "passive"))
      (node (ref "S1") (pin "1") (pinfunction "1_1") (pintype "passive"))
      (node (ref "U2") (pin "23") (pinfunction "VSS_1_23") (pintype "power_in"))
      (node (ref "U2") (pin "35") (pinfunction "VSS_2_35") (pintype "power_in"))
      (node (ref "U2") (pin "47") (pinfunction "VSS_3_47") (pintype "power_in"))
      (node (ref "U2") (pin "8") (pinfunction "VSSA_8") (pintype "power_in"))
      (node (ref "Y") (pin "2") (pinfunction "GND_2") (pintype "power_in"))
      (node (ref "Y") (pin "4") (pinfunction "GND_4") (pintype "power_in"))
    )
    (net (code "41") (name "Net-(U2A-PD1-OSC_OUT)") (class "Default")
      (node (ref "R1") (pin "2") (pinfunction "2_2") (pintype "passive"))
      (node (ref "U2") (pin "6") (pinfunction "PD1-OSC_OUT_6") (pintype "bidirectional"))
    )
    (net (code "42") (name "unconnected-(U2A-PC13-TAMPER-RTC-Pad2)") (class "Default")
      (node (ref "U2") (pin "2") (pinfunction "PC13-TAMPER-RTC_2") (pintype "bidirectional"))
    )
  )
)
